# Sheet2.net
KiCad netlist of a schematic drawn in Altium Designer
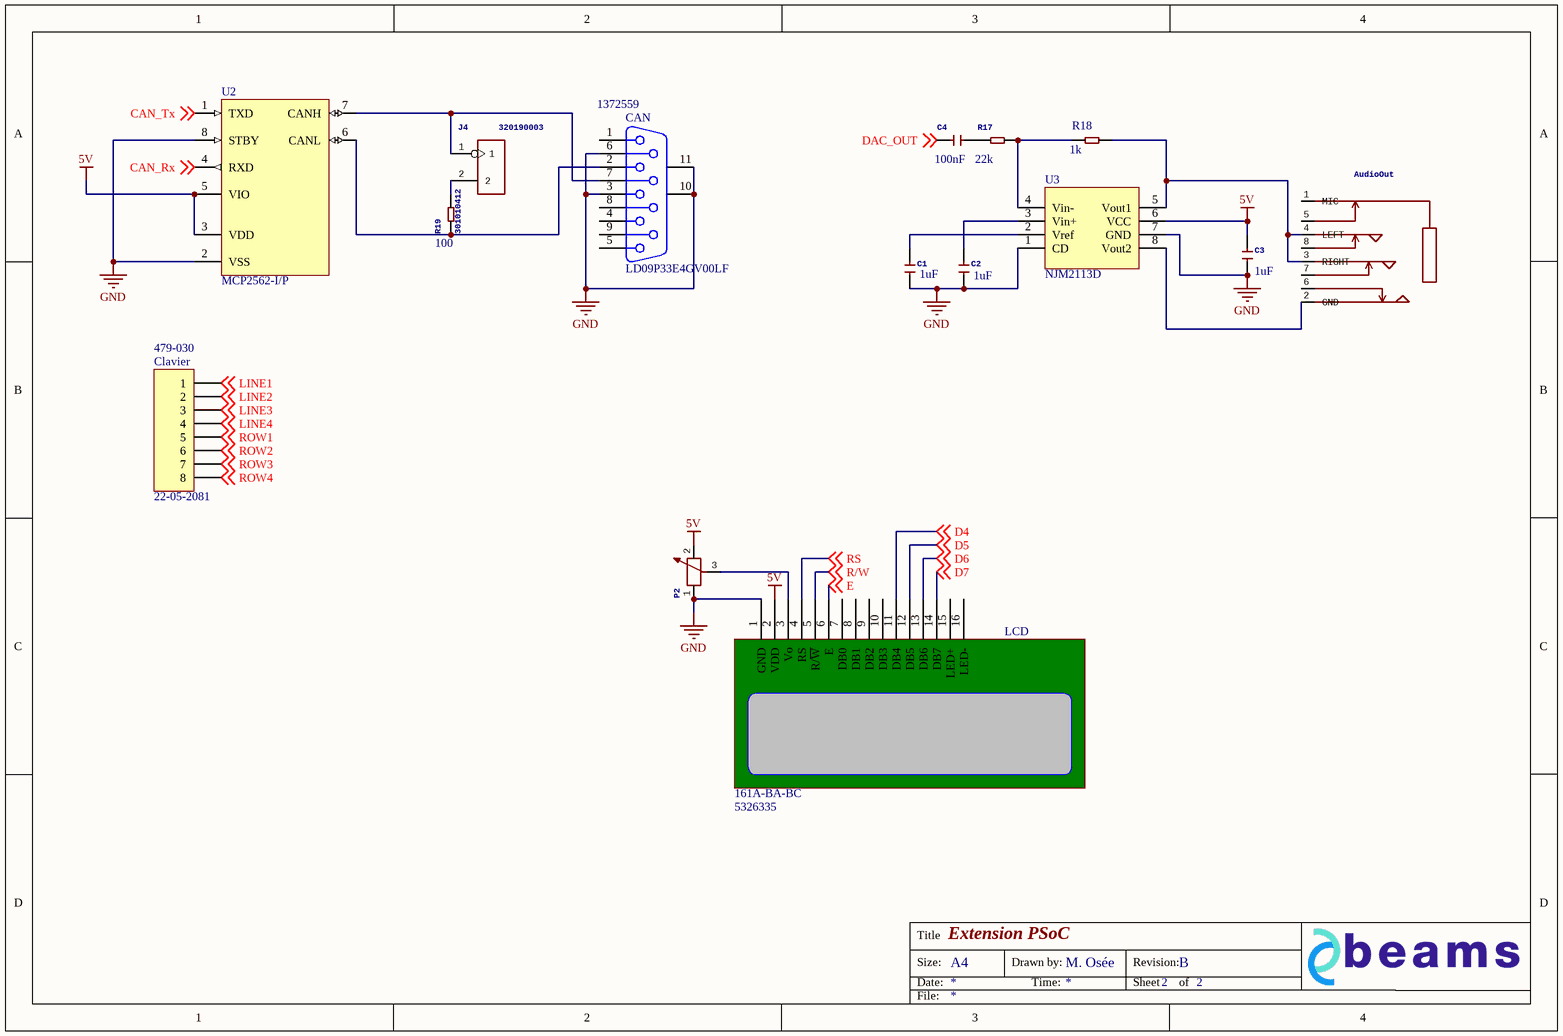
[diagram p0: Sheet2.SchDoc]

(export (version "E")
  (design (tool "Eeschema 10.0.6"))
  (components
    (comp (ref "AudioOut")
      (value "320040003")
      (footprint "AUDIO8P-SMD-3.5-14.5X6X5MM")
      (fields (field (name "MPN") "PJ-3536-L6S"))
      (libsource (lib "Seeed-Connector") (part "AUDIO-JACK-SMD-8P(PJ-3536-L6S)"))
    )
    (comp (ref "C1")
      (value "1uF")
      (footprint "C0805")
      (fields (field (name "MPN") "CC0805KKX7R8BB105") (field (name "Comment") "302010179"))
      (libsource (lib "Seeed-Capacitor") (part "CERAMIC-1UF-25V-10%-X7R(0805)"))
    )
    (comp (ref "C2")
      (value "1uF")
      (footprint "C0805")
      (fields (field (name "MPN") "CC0805KKX7R8BB105") (field (name "Comment") "302010179"))
      (libsource (lib "Seeed-Capacitor") (part "CERAMIC-1UF-25V-10%-X7R(0805)"))
    )
    (comp (ref "C3")
      (value "1uF")
      (footprint "C0805")
      (fields (field (name "MPN") "CC0805KKX7R8BB105") (field (name "Comment") "302010179"))
      (libsource (lib "Seeed-Capacitor") (part "CERAMIC-1UF-25V-10%-X7R(0805)"))
    )
    (comp (ref "C4")
      (value "100nF")
      (footprint "C0603")
      (fields (field (name "MPN") "CC0603KRX7R9BB104") (field (name "Comment") "302010138"))
      (libsource (lib "Seeed-Capacitor") (part "CERAMIC-100NF-50V-10%-X7R(0603)"))
    )
    (comp (ref "CAN")
      (value "LD09P33E4GV00LF")
      (footprint "DSUB1.385-2H9B")
      (description "Receptacle Assembly, 9 Position, Right Angle")
      (fields (field (name "SUPPLIER PART NUMBER 1") "1372559") (field (name "PUBLISHER") "Altium Limited"))
      (libsource (lib "Miscellaneous Connectors") (part "D Connector 9"))
    )
    (comp (ref "Clavier")
      (value "22-05-2081")
      (footprint "HDR1X8H")
      (description "Header, 8-Pin, Right Angle")
      (fields (field (name "SUPPLIER PART NUMBER 1") "479-030") (field (name "PUBLISHER") "Altium Limited"))
      (libsource (lib "Miscellaneous Connectors") (part "Header 8H"))
    )
    (comp (ref "J4")
      (value "320190003")
      (footprint "H2-2.54")
      (libsource (lib "Seeed-Connector") (part "DIP-BLACK-JUMPER"))
    )
    (comp (ref "LCD")
      (value "161A-BA-BC")
      (footprint "PC161A")
      (description "Displaytech 16x1 LCD monochrome display")
      (fields (field (name "SUPPLIER PART NUMBER 1") "5326335"))
      (libsource (lib "Divers") (part "PC161A"))
    )
    (comp (ref "P2")
      (value "301040007")
      (footprint "ADJR3-9.5X9.5X10.5MM")
      (fields (field (name "MPN") "3386U-103"))
      (libsource (lib "Seeed-Resistor") (part "DIP-VR-TOP-ADJ-10K(3P-9.5X9.5X5MM)"))
    )
    (comp (ref "R17")
      (value "22k")
      (footprint "R0603")
      (fields (field (name "MPN") "RC0603JR-0722KL") (field (name "Comment") "301010132"))
      (libsource (lib "Seeed-Resistor") (part "SMD-RES-22K-5%-1/10W(0603)"))
    )
    (comp (ref "R18")
      (value "1k")
      (footprint "R0603")
      (fields (field (name "MPN") "RC0603FR-071KL") (field (name "Comment") "301010298"))
      (libsource (lib "Seeed-Resistor") (part "SMD-RES-1K-1%-1/10W(0603)"))
    )
    (comp (ref "R19")
      (value "301010412")
      (footprint "R1206")
      (fields (field (name "MPN") "RC1206JR-07100RL") (field (name "ALTIUM_VALUE") "100"))
      (libsource (lib "Seeed-Resistor") (part "SMD-RES-100R-5%-1/4W(1206)"))
    )
    (comp (ref "U2")
      (value "MCP2562-I/P")
      (footprint "DIP8")
      (description "High-Speed CAN Transceiver, 8-Pin PDIP")
      (fields (field (name "MANUFACTURER") "Microchip") (field (name "PARTNUMBER") "MCP2551-I/P"))
      (libsource (lib "integres") (part "MCP2562-I/P"))
    )
    (comp (ref "U3") (value "NJM2113D") (footprint "DIP8") (libsource (lib "integres") (part "NJM2113D")))
  )
  (nets
    (net (code "1") (name "5V") (class "Default")
      (node (ref "C3") (pin "2") (pinfunction "2_2") (pintype "passive"))
      (node (ref "LCD") (pin "2") (pinfunction "VDD_2") (pintype "passive"))
      (node (ref "P2") (pin "2") (pinfunction "2_2") (pintype "passive"))
      (node (ref "U2") (pin "3") (pinfunction "VDD_3") (pintype "power_in"))
      (node (ref "U2") (pin "5") (pinfunction "VIO_5") (pintype "power_in"))
      (node (ref "U3") (pin "6") (pinfunction "VCC_6") (pintype "passive"))
    )
    (net (code "2") (name "CAN_Rx") (class "Default")
      (node (ref "U2") (pin "4") (pinfunction "RXD_4") (pintype "output"))
    )
    (net (code "3") (name "CAN_Tx") (class "Default")
      (node (ref "U2") (pin "1") (pinfunction "TXD_1") (pintype "input"))
    )
    (net (code "4") (name "D4") (class "Default")
      (node (ref "LCD") (pin "11") (pinfunction "DB4_11") (pintype "passive"))
    )
    (net (code "5") (name "D5") (class "Default")
      (node (ref "LCD") (pin "12") (pinfunction "DB5_12") (pintype "passive"))
    )
    (net (code "6") (name "D6") (class "Default")
      (node (ref "LCD") (pin "13") (pinfunction "DB6_13") (pintype "passive"))
    )
    (net (code "7") (name "D7") (class "Default")
      (node (ref "LCD") (pin "14") (pinfunction "DB7_14") (pintype "passive"))
    )
    (net (code "8") (name "DAC_OUT") (class "Default")
      (node (ref "C4") (pin "1") (pinfunction "1_1") (pintype "passive"))
    )
    (net (code "9") (name "E") (class "Default")
      (node (ref "LCD") (pin "6") (pinfunction "E_6") (pintype "passive"))
    )
    (net (code "10") (name "GND") (class "Default")
      (node (ref "C1") (pin "1") (pinfunction "1_1") (pintype "passive"))
      (node (ref "C2") (pin "1") (pinfunction "1_1") (pintype "passive"))
      (node (ref "C3") (pin "1") (pinfunction "1_1") (pintype "passive"))
      (node (ref "CAN") (pin "10") (pinfunction "MH1_10") (pintype "passive"))
      (node (ref "CAN") (pin "11") (pinfunction "MH2_11") (pintype "passive"))
      (node (ref "CAN") (pin "3") (pinfunction "3_3") (pintype "passive"))
      (node (ref "CAN") (pin "6") (pinfunction "6_6") (pintype "passive"))
      (node (ref "LCD") (pin "1") (pinfunction "GND_1") (pintype "passive"))
      (node (ref "P2") (pin "1") (pinfunction "1_1") (pintype "passive"))
      (node (ref "U2") (pin "2") (pinfunction "VSS_2") (pintype "power_in"))
      (node (ref "U2") (pin "8") (pinfunction "STBY_8") (pintype "input"))
      (node (ref "U3") (pin "1") (pinfunction "CD_1") (pintype "passive"))
      (node (ref "U3") (pin "7") (pinfunction "GND_7") (pintype "passive"))
    )
    (net (code "11") (name "LINE1") (class "Default")
      (node (ref "Clavier") (pin "1") (pinfunction "1_1") (pintype "passive"))
    )
    (net (code "12") (name "LINE2") (class "Default")
      (node (ref "Clavier") (pin "2") (pinfunction "2_2") (pintype "passive"))
    )
    (net (code "13") (name "LINE3") (class "Default")
      (node (ref "Clavier") (pin "3") (pinfunction "3_3") (pintype "passive"))
    )
    (net (code "14") (name "LINE4") (class "Default")
      (node (ref "Clavier") (pin "4") (pinfunction "4_4") (pintype "passive"))
    )
    (net (code "15") (name "Net-(AudioOut-GND)") (class "Default")
      (node (ref "AudioOut") (pin "2") (pinfunction "GND_2") (pintype "passive"))
      (node (ref "U3") (pin "8") (pinfunction "Vout2_8") (pintype "passive"))
    )
    (net (code "16") (name "Net-(AudioOut-LEFT)") (class "Default")
      (node (ref "AudioOut") (pin "3") (pinfunction "RIGHT_3") (pintype "passive"))
      (node (ref "AudioOut") (pin "4") (pinfunction "LEFT_4") (pintype "passive"))
      (node (ref "R18") (pin "2") (pinfunction "2_2") (pintype "passive"))
      (node (ref "U3") (pin "5") (pinfunction "Vout1_5") (pintype "passive"))
    )
    (net (code "17") (name "Net-(C4-Pad2)") (class "Default")
      (node (ref "C4") (pin "2") (pinfunction "2_2") (pintype "passive"))
      (node (ref "R17") (pin "1") (pinfunction "1_1") (pintype "passive"))
    )
    (net (code "18") (name "Net-(J4-Pad2)") (class "Default")
      (node (ref "J4") (pin "2") (pinfunction "2_2") (pintype "passive"))
      (node (ref "R19") (pin "2") (pinfunction "2_2") (pintype "passive"))
    )
    (net (code "19") (name "Net-(LCD-Vo)") (class "Default")
      (node (ref "LCD") (pin "3") (pinfunction "Vo_3") (pintype "passive"))
      (node (ref "P2") (pin "3") (pinfunction "3_3") (pintype "passive"))
    )
    (net (code "20") (name "Net-(U2-CANH)") (class "Default")
      (node (ref "CAN") (pin "7") (pinfunction "7_7") (pintype "passive"))
      (node (ref "J4") (pin "1") (pinfunction "1_1") (pintype "passive"))
      (node (ref "U2") (pin "7") (pinfunction "CANH_7") (pintype "bidirectional"))
    )
    (net (code "21") (name "Net-(U2-CANL)") (class "Default")
      (node (ref "CAN") (pin "2") (pinfunction "2_2") (pintype "passive"))
      (node (ref "R19") (pin "1") (pinfunction "1_1") (pintype "passive"))
      (node (ref "U2") (pin "6") (pinfunction "CANL_6") (pintype "bidirectional"))
    )
    (net (code "22") (name "Net-(U3-Vin+)") (class "Default")
      (node (ref "C2") (pin "2") (pinfunction "2_2") (pintype "passive"))
      (node (ref "U3") (pin "3") (pinfunction "Vin+_3") (pintype "passive"))
    )
    (net (code "23") (name "Net-(U3-Vin-)") (class "Default")
      (node (ref "R17") (pin "2") (pinfunction "2_2") (pintype "passive"))
      (node (ref "R18") (pin "1") (pinfunction "1_1") (pintype "passive"))
      (node (ref "U3") (pin "4") (pinfunction "Vin-_4") (pintype "passive"))
    )
    (net (code "24") (name "Net-(U3-Vref)") (class "Default")
      (node (ref "C1") (pin "2") (pinfunction "2_2") (pintype "passive"))
      (node (ref "U3") (pin "2") (pinfunction "Vref_2") (pintype "passive"))
    )
    (net (code "25") (name "ROW1") (class "Default")
      (node (ref "Clavier") (pin "5") (pinfunction "5_5") (pintype "passive"))
    )
    (net (code "26") (name "ROW2") (class "Default")
      (node (ref "Clavier") (pin "6") (pinfunction "6_6") (pintype "passive"))
    )
    (net (code "27") (name "ROW3") (class "Default")
      (node (ref "Clavier") (pin "7") (pinfunction "7_7") (pintype "passive"))
    )
    (net (code "28") (name "ROW4") (class "Default")
      (node (ref "Clavier") (pin "8") (pinfunction "8_8") (pintype "passive"))
    )
    (net (code "29") (name "RS") (class "Default")
      (node (ref "LCD") (pin "4") (pinfunction "RS_4") (pintype "passive"))
    )
    (net (code "30") (name "R{slash}W") (class "Default")
      (node (ref "LCD") (pin "5") (pinfunction "R/~{W}_5") (pintype "passive"))
    )
    (net (code "31") (name "unconnected-(AudioOut-MIC-Pad1)") (class "Default")
      (node (ref "AudioOut") (pin "1") (pinfunction "MIC_1") (pintype "passive"))
    )
    (net (code "32") (name "unconnected-(AudioOut-Pad5)") (class "Default")
      (node (ref "AudioOut") (pin "5") (pinfunction "5_5") (pintype "passive"))
    )
    (net (code "33") (name "unconnected-(AudioOut-Pad6)") (class "Default")
      (node (ref "AudioOut") (pin "6") (pinfunction "6_6") (pintype "passive"))
    )
    (net (code "34") (name "unconnected-(AudioOut-Pad7)") (class "Default")
      (node (ref "AudioOut") (pin "7") (pinfunction "7_7") (pintype "passive"))
    )
    (net (code "35") (name "unconnected-(AudioOut-Pad8)") (class "Default")
      (node (ref "AudioOut") (pin "8") (pinfunction "8_8") (pintype "passive"))
    )
    (net (code "36") (name "unconnected-(CAN-Pad1)") (class "Default")
      (node (ref "CAN") (pin "1") (pinfunction "1_1") (pintype "passive"))
    )
    (net (code "37") (name "unconnected-(CAN-Pad4)") (class "Default")
      (node (ref "CAN") (pin "4") (pinfunction "4_4") (pintype "passive"))
    )
    (net (code "38") (name "unconnected-(CAN-Pad5)") (class "Default")
      (node (ref "CAN") (pin "5") (pinfunction "5_5") (pintype "passive"))
    )
    (net (code "39") (name "unconnected-(CAN-Pad8)") (class "Default")
      (node (ref "CAN") (pin "8") (pinfunction "8_8") (pintype "passive"))
    )
    (net (code "40") (name "unconnected-(CAN-Pad9)") (class "Default")
      (node (ref "CAN") (pin "9") (pinfunction "9_9") (pintype "passive"))
    )
    (net (code "41") (name "unconnected-(LCD-DB0-Pad7)") (class "Default")
      (node (ref "LCD") (pin "7") (pinfunction "DB0_7") (pintype "passive"))
    )
    (net (code "42") (name "unconnected-(LCD-DB1-Pad8)") (class "Default")
      (node (ref "LCD") (pin "8") (pinfunction "DB1_8") (pintype "passive"))
    )
    (net (code "43") (name "unconnected-(LCD-DB2-Pad9)") (class "Default")
      (node (ref "LCD") (pin "9") (pinfunction "DB2_9") (pintype "passive"))
    )
    (net (code "44") (name "unconnected-(LCD-DB3-Pad10)") (class "Default")
      (node (ref "LCD") (pin "10") (pinfunction "DB3_10") (pintype "passive"))
    )
    (net (code "45") (name "unconnected-(LCD-LED+-Pad15)") (class "Default")
      (node (ref "LCD") (pin "15") (pinfunction "LED+_15") (pintype "passive"))
    )
    (net (code "46") (name "unconnected-(LCD-LED--Pad16)") (class "Default")
      (node (ref "LCD") (pin "16") (pinfunction "LED-_16") (pintype "passive"))
    )
  )
)
